# Version2.net
KiCad netlist of a schematic drawn in EAGLE
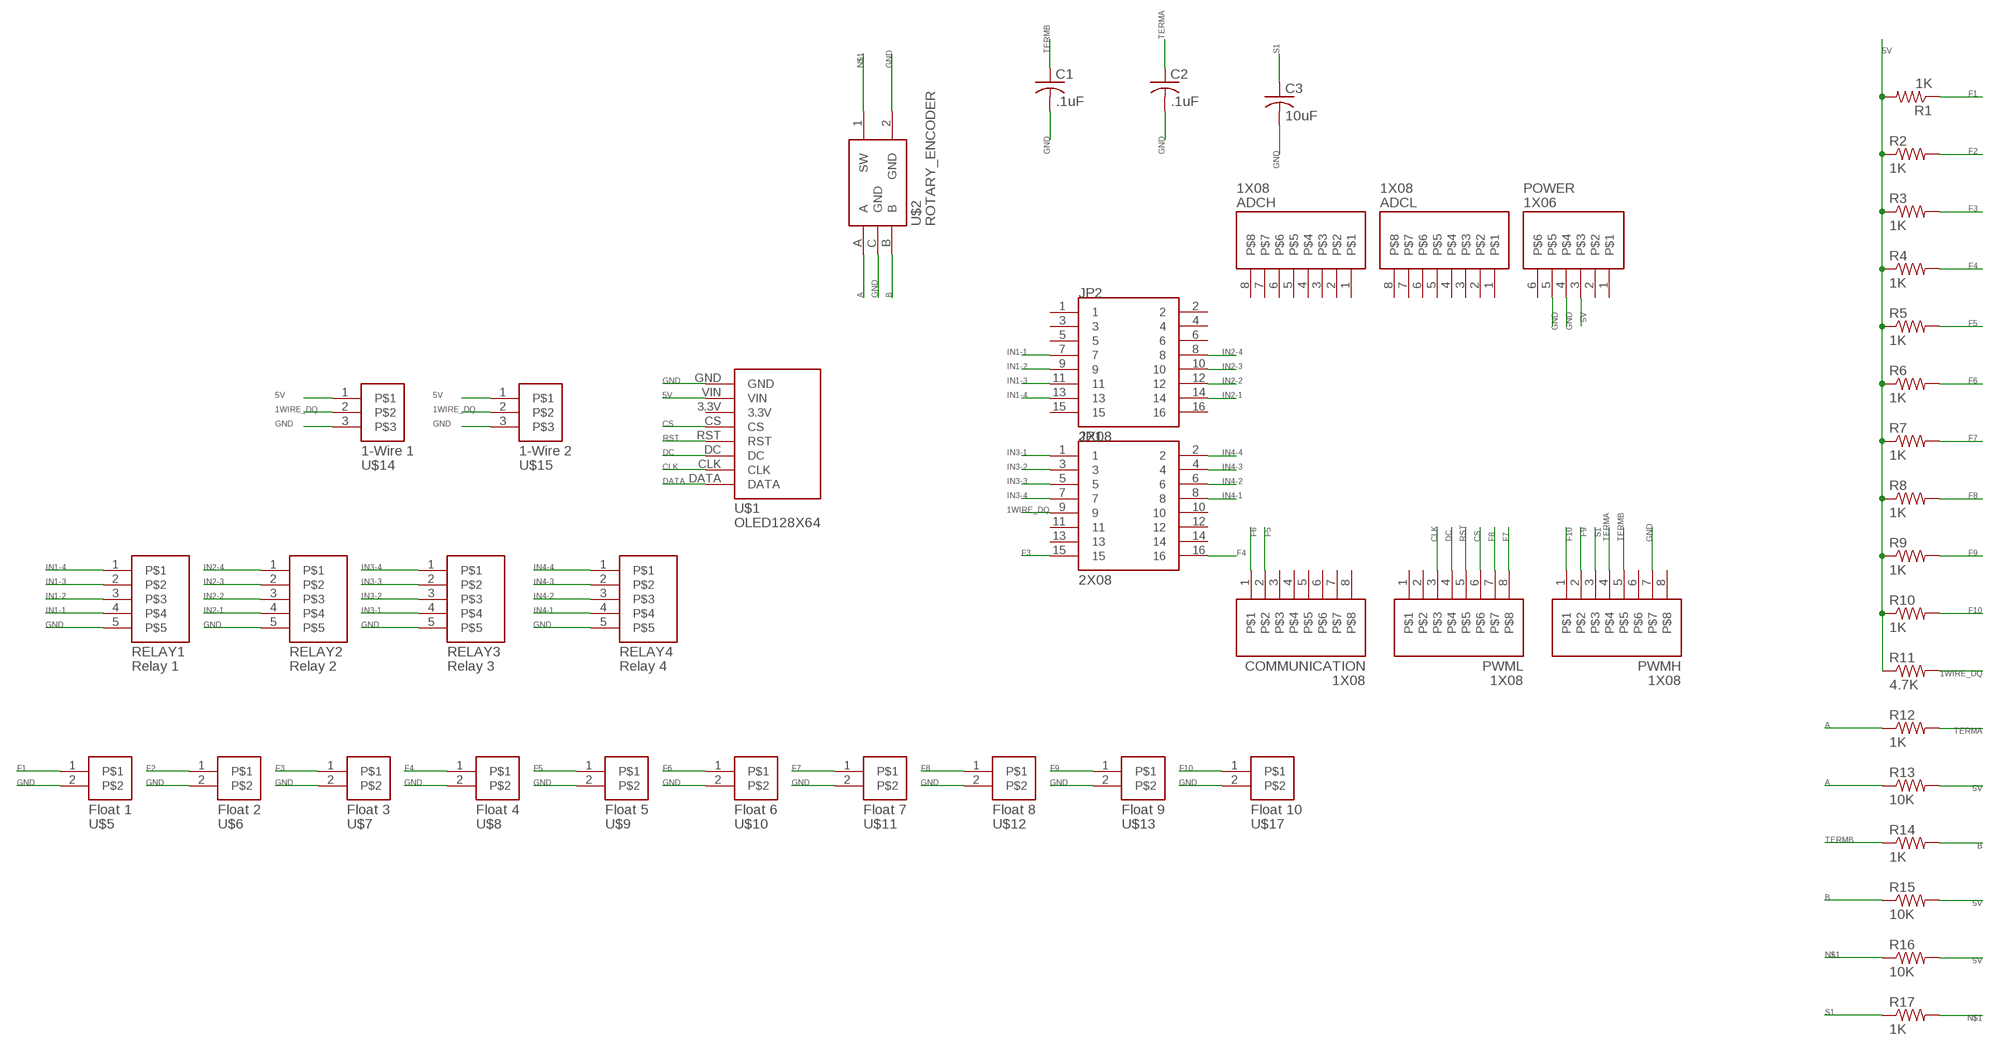
[diagram p0: schematic, sheet 1]

(export (version "E")
  (design (tool "Eeschema 10.0.6"))
  (components
    (comp (ref "ADCH")
      (value "1X08")
      (footprint "eagle-import:1X08_SMT")
      (libsource (lib "eagle-import") (part "1X08"))
    )
    (comp (ref "ADCL")
      (value "1X08")
      (footprint "eagle-import:1X08_SMT")
      (libsource (lib "eagle-import") (part "1X08"))
    )
    (comp (ref "C1")
      (value ".1uF")
      (footprint "eagle-import:C0805K")
      (libsource (lib "eagle-import") (part "C-USC0805K"))
    )
    (comp (ref "C2")
      (value ".1uF")
      (footprint "eagle-import:C0805K")
      (libsource (lib "eagle-import") (part "resistor_C-USC0805K"))
    )
    (comp (ref "C3")
      (value "10uF")
      (footprint "eagle-import:C0805K")
      (libsource (lib "eagle-import") (part "resistor_C-USC0805K"))
    )
    (comp (ref "COMMUNICATION")
      (value "1X08")
      (footprint "eagle-import:1X08_SMT")
      (libsource (lib "eagle-import") (part "1X08"))
    )
    (comp (ref "JP1")
      (value "2X08")
      (footprint "eagle-import:2X08_SMT")
      (libsource (lib "eagle-import") (part "2X08"))
    )
    (comp (ref "JP2")
      (value "2X08")
      (footprint "eagle-import:2X08_SMT")
      (libsource (lib "eagle-import") (part "2X08"))
    )
    (comp (ref "POWER")
      (value "1X06")
      (footprint "eagle-import:1X06_SMT")
      (libsource (lib "eagle-import") (part "1X06"))
    )
    (comp (ref "PWMH")
      (value "1X08")
      (footprint "eagle-import:1X08_SMT")
      (libsource (lib "eagle-import") (part "1X08"))
    )
    (comp (ref "PWML")
      (value "1X08")
      (footprint "eagle-import:1X08_SMT")
      (libsource (lib "eagle-import") (part "1X08"))
    )
    (comp (ref "R1")
      (value "1K")
      (footprint "eagle-import:R0805")
      (libsource (lib "eagle-import") (part "R-US_R0805"))
    )
    (comp (ref "R2")
      (value "1K")
      (footprint "eagle-import:R0805")
      (libsource (lib "eagle-import") (part "R-US_R0805"))
    )
    (comp (ref "R3")
      (value "1K")
      (footprint "eagle-import:R0805")
      (libsource (lib "eagle-import") (part "R-US_R0805"))
    )
    (comp (ref "R4")
      (value "1K")
      (footprint "eagle-import:R0805")
      (libsource (lib "eagle-import") (part "R-US_R0805"))
    )
    (comp (ref "R5")
      (value "1K")
      (footprint "eagle-import:R0805")
      (libsource (lib "eagle-import") (part "R-US_R0805"))
    )
    (comp (ref "R6")
      (value "1K")
      (footprint "eagle-import:R0805")
      (libsource (lib "eagle-import") (part "R-US_R0805"))
    )
    (comp (ref "R7")
      (value "1K")
      (footprint "eagle-import:R0805")
      (libsource (lib "eagle-import") (part "R-US_R0805"))
    )
    (comp (ref "R8")
      (value "1K")
      (footprint "eagle-import:R0805")
      (libsource (lib "eagle-import") (part "R-US_R0805"))
    )
    (comp (ref "R9")
      (value "1K")
      (footprint "eagle-import:R0805")
      (libsource (lib "eagle-import") (part "R-US_R0805"))
    )
    (comp (ref "R10")
      (value "1K")
      (footprint "eagle-import:R0805")
      (libsource (lib "eagle-import") (part "R-US_R0805"))
    )
    (comp (ref "R11")
      (value "4.7K")
      (footprint "eagle-import:R0805")
      (libsource (lib "eagle-import") (part "R-US_R0805"))
    )
    (comp (ref "R12")
      (value "1K")
      (footprint "eagle-import:R0805")
      (libsource (lib "eagle-import") (part "R-US_R0805"))
    )
    (comp (ref "R13")
      (value "10K")
      (footprint "eagle-import:R0805")
      (libsource (lib "eagle-import") (part "R-US_R0805"))
    )
    (comp (ref "R14")
      (value "1K")
      (footprint "eagle-import:R0805")
      (libsource (lib "eagle-import") (part "R-US_R0805"))
    )
    (comp (ref "R15")
      (value "10K")
      (footprint "eagle-import:R0805")
      (libsource (lib "eagle-import") (part "R-US_R0805"))
    )
    (comp (ref "R16")
      (value "10K")
      (footprint "eagle-import:R0805")
      (libsource (lib "eagle-import") (part "R-US_R0805"))
    )
    (comp (ref "R17")
      (value "1K")
      (footprint "eagle-import:R0805")
      (libsource (lib "eagle-import") (part "R-US_R0805"))
    )
    (comp (ref "RELAY1")
      (value "Relay 1")
      (footprint "eagle-import:5PIN-MOLEX-HEADER-W-PEGS")
      (libsource (lib "eagle-import") (part "5PIN"))
    )
    (comp (ref "RELAY2")
      (value "Relay 2")
      (footprint "eagle-import:5PIN-MOLEX-HEADER-W-PEGS")
      (libsource (lib "eagle-import") (part "5PIN"))
    )
    (comp (ref "RELAY3")
      (value "Relay 3")
      (footprint "eagle-import:5PIN-MOLEX-HEADER-W-PEGS")
      (libsource (lib "eagle-import") (part "5PIN"))
    )
    (comp (ref "RELAY4")
      (value "Relay 4")
      (footprint "eagle-import:5PIN-MOLEX-HEADER-W-PEGS")
      (libsource (lib "eagle-import") (part "5PIN"))
    )
    (comp (ref "U$1")
      (value "OLED128X64")
      (footprint "eagle-import:OLED128X64")
      (libsource (lib "eagle-import") (part "OLED128X64"))
    )
    (comp (ref "U$2")
      (value "ROTARY_ENCODER")
      (footprint "eagle-import:PEC11-4215F-S24")
      (libsource (lib "eagle-import") (part "PEC11-4215F-S24"))
    )
    (comp (ref "U$5")
      (value "Float 1")
      (footprint "eagle-import:2PIN-MOLEX-HEADER-W-PEGS")
      (libsource (lib "eagle-import") (part "2PIN"))
    )
    (comp (ref "U$6")
      (value "Float 2")
      (footprint "eagle-import:2PIN-MOLEX-HEADER-W-PEGS")
      (libsource (lib "eagle-import") (part "2PIN"))
    )
    (comp (ref "U$7")
      (value "Float 3")
      (footprint "eagle-import:2PIN-MOLEX-HEADER-W-PEGS")
      (libsource (lib "eagle-import") (part "2PIN"))
    )
    (comp (ref "U$8")
      (value "Float 4")
      (footprint "eagle-import:2PIN-MOLEX-HEADER-W-PEGS")
      (libsource (lib "eagle-import") (part "2PIN"))
    )
    (comp (ref "U$9")
      (value "Float 5")
      (footprint "eagle-import:2PIN-MOLEX-HEADER-W-PEGS")
      (libsource (lib "eagle-import") (part "2PIN"))
    )
    (comp (ref "U$10")
      (value "Float 6")
      (footprint "eagle-import:2PIN-MOLEX-HEADER-W-PEGS")
      (libsource (lib "eagle-import") (part "2PIN"))
    )
    (comp (ref "U$11")
      (value "Float 7")
      (footprint "eagle-import:2PIN-MOLEX-HEADER-W-PEGS")
      (libsource (lib "eagle-import") (part "2PIN"))
    )
    (comp (ref "U$12")
      (value "Float 8")
      (footprint "eagle-import:2PIN-MOLEX-HEADER-W-PEGS")
      (libsource (lib "eagle-import") (part "2PIN"))
    )
    (comp (ref "U$13")
      (value "Float 9")
      (footprint "eagle-import:2PIN-MOLEX-HEADER-W-PEGS")
      (libsource (lib "eagle-import") (part "2PIN"))
    )
    (comp (ref "U$14")
      (value "1-Wire 1")
      (footprint "eagle-import:3PIN-MOLEX-HEADER-W-PEGS")
      (libsource (lib "eagle-import") (part "3PIN"))
    )
    (comp (ref "U$15")
      (value "1-Wire 2")
      (footprint "eagle-import:3PIN-MOLEX-HEADER-W-PEGS")
      (libsource (lib "eagle-import") (part "3PIN"))
    )
    (comp (ref "U$17")
      (value "Float 10")
      (footprint "eagle-import:2PIN-MOLEX-HEADER-W-PEGS")
      (libsource (lib "eagle-import") (part "2PIN"))
    )
  )
  (nets
    (net (code "1") (name "/1WIRE_DQ") (class "Default")
      (node (ref "JP1") (pin "9") (pinfunction "9_9") (pintype "bidirectional"))
      (node (ref "R11") (pin "2") (pinfunction "2_2") (pintype "passive"))
      (node (ref "U$14") (pin "2") (pinfunction "P$2_2") (pintype "bidirectional"))
      (node (ref "U$15") (pin "2") (pinfunction "P$2_2") (pintype "bidirectional"))
    )
    (net (code "2") (name "/5V") (class "Default")
      (node (ref "POWER") (pin "3") (pinfunction "P$3_3") (pintype "bidirectional"))
      (node (ref "R1") (pin "2") (pinfunction "2_2") (pintype "passive"))
      (node (ref "R10") (pin "1") (pinfunction "1_1") (pintype "passive"))
      (node (ref "R11") (pin "1") (pinfunction "1_1") (pintype "passive"))
      (node (ref "R13") (pin "2") (pinfunction "2_2") (pintype "passive"))
      (node (ref "R15") (pin "2") (pinfunction "2_2") (pintype "passive"))
      (node (ref "R16") (pin "2") (pinfunction "2_2") (pintype "passive"))
      (node (ref "R2") (pin "1") (pinfunction "1_1") (pintype "passive"))
      (node (ref "R3") (pin "1") (pinfunction "1_1") (pintype "passive"))
      (node (ref "R4") (pin "1") (pinfunction "1_1") (pintype "passive"))
      (node (ref "R5") (pin "1") (pinfunction "1_1") (pintype "passive"))
      (node (ref "R6") (pin "1") (pinfunction "1_1") (pintype "passive"))
      (node (ref "R7") (pin "1") (pinfunction "1_1") (pintype "passive"))
      (node (ref "R8") (pin "1") (pinfunction "1_1") (pintype "passive"))
      (node (ref "R9") (pin "1") (pinfunction "1_1") (pintype "passive"))
      (node (ref "U$1") (pin "VIN") (pinfunction "VIN_VIN") (pintype "bidirectional"))
      (node (ref "U$14") (pin "1") (pinfunction "P$1_1") (pintype "bidirectional"))
      (node (ref "U$15") (pin "1") (pinfunction "P$1_1") (pintype "bidirectional"))
    )
    (net (code "3") (name "/A") (class "Default")
      (node (ref "R12") (pin "1") (pinfunction "1_1") (pintype "passive"))
      (node (ref "R13") (pin "1") (pinfunction "1_1") (pintype "passive"))
      (node (ref "U$2") (pin "A") (pinfunction "A_A") (pintype "bidirectional"))
    )
    (net (code "4") (name "/B") (class "Default")
      (node (ref "R14") (pin "2") (pinfunction "2_2") (pintype "passive"))
      (node (ref "R15") (pin "1") (pinfunction "1_1") (pintype "passive"))
      (node (ref "U$2") (pin "B") (pinfunction "B_B") (pintype "bidirectional"))
    )
    (net (code "5") (name "/CLK") (class "Default")
      (node (ref "PWML") (pin "3") (pinfunction "P$3_3") (pintype "bidirectional"))
      (node (ref "U$1") (pin "CLK") (pinfunction "CLK_CLK") (pintype "bidirectional"))
    )
    (net (code "6") (name "/CS") (class "Default")
      (node (ref "PWML") (pin "6") (pinfunction "P$6_6") (pintype "bidirectional"))
      (node (ref "U$1") (pin "CS") (pinfunction "CS_CS") (pintype "bidirectional"))
    )
    (net (code "7") (name "/DATA") (class "Default")
      (node (ref "U$1") (pin "DATA") (pinfunction "DATA_DATA") (pintype "bidirectional"))
    )
    (net (code "8") (name "/DC") (class "Default")
      (node (ref "PWML") (pin "4") (pinfunction "P$4_4") (pintype "bidirectional"))
      (node (ref "U$1") (pin "DC") (pinfunction "DC_DC") (pintype "bidirectional"))
    )
    (net (code "9") (name "/F1") (class "Default")
      (node (ref "R1") (pin "1") (pinfunction "1_1") (pintype "passive"))
      (node (ref "U$5") (pin "1") (pinfunction "P$1_1") (pintype "bidirectional"))
    )
    (net (code "10") (name "/F2") (class "Default")
      (node (ref "R2") (pin "2") (pinfunction "2_2") (pintype "passive"))
      (node (ref "U$6") (pin "1") (pinfunction "P$1_1") (pintype "bidirectional"))
    )
    (net (code "11") (name "/F3") (class "Default")
      (node (ref "JP1") (pin "15") (pinfunction "15_15") (pintype "bidirectional"))
      (node (ref "R3") (pin "2") (pinfunction "2_2") (pintype "passive"))
      (node (ref "U$7") (pin "1") (pinfunction "P$1_1") (pintype "bidirectional"))
    )
    (net (code "12") (name "/F4") (class "Default")
      (node (ref "JP1") (pin "16") (pinfunction "16_16") (pintype "bidirectional"))
      (node (ref "R4") (pin "2") (pinfunction "2_2") (pintype "passive"))
      (node (ref "U$8") (pin "1") (pinfunction "P$1_1") (pintype "bidirectional"))
    )
    (net (code "13") (name "/F5") (class "Default")
      (node (ref "COMMUNICATION") (pin "2") (pinfunction "P$2_2") (pintype "bidirectional"))
      (node (ref "R5") (pin "2") (pinfunction "2_2") (pintype "passive"))
      (node (ref "U$9") (pin "1") (pinfunction "P$1_1") (pintype "bidirectional"))
    )
    (net (code "14") (name "/F6") (class "Default")
      (node (ref "COMMUNICATION") (pin "1") (pinfunction "P$1_1") (pintype "bidirectional"))
      (node (ref "R6") (pin "2") (pinfunction "2_2") (pintype "passive"))
      (node (ref "U$10") (pin "1") (pinfunction "P$1_1") (pintype "bidirectional"))
    )
    (net (code "15") (name "/F7") (class "Default")
      (node (ref "PWML") (pin "8") (pinfunction "P$8_8") (pintype "bidirectional"))
      (node (ref "R7") (pin "2") (pinfunction "2_2") (pintype "passive"))
      (node (ref "U$11") (pin "1") (pinfunction "P$1_1") (pintype "bidirectional"))
    )
    (net (code "16") (name "/F8") (class "Default")
      (node (ref "PWML") (pin "7") (pinfunction "P$7_7") (pintype "bidirectional"))
      (node (ref "R8") (pin "2") (pinfunction "2_2") (pintype "passive"))
      (node (ref "U$12") (pin "1") (pinfunction "P$1_1") (pintype "bidirectional"))
    )
    (net (code "17") (name "/F9") (class "Default")
      (node (ref "PWMH") (pin "2") (pinfunction "P$2_2") (pintype "bidirectional"))
      (node (ref "R9") (pin "2") (pinfunction "2_2") (pintype "passive"))
      (node (ref "U$13") (pin "1") (pinfunction "P$1_1") (pintype "bidirectional"))
    )
    (net (code "18") (name "/F10") (class "Default")
      (node (ref "PWMH") (pin "1") (pinfunction "P$1_1") (pintype "bidirectional"))
      (node (ref "R10") (pin "2") (pinfunction "2_2") (pintype "passive"))
      (node (ref "U$17") (pin "1") (pinfunction "P$1_1") (pintype "bidirectional"))
    )
    (net (code "19") (name "/GND") (class "Default")
      (node (ref "C1") (pin "2") (pinfunction "2_2") (pintype "passive"))
      (node (ref "C2") (pin "2") (pinfunction "2_2") (pintype "passive"))
      (node (ref "C3") (pin "2") (pinfunction "2_2") (pintype "passive"))
      (node (ref "POWER") (pin "4") (pinfunction "P$4_4") (pintype "bidirectional"))
      (node (ref "POWER") (pin "5") (pinfunction "P$5_5") (pintype "bidirectional"))
      (node (ref "PWMH") (pin "7") (pinfunction "P$7_7") (pintype "bidirectional"))
      (node (ref "RELAY1") (pin "5") (pinfunction "P$5_5") (pintype "bidirectional"))
      (node (ref "RELAY2") (pin "5") (pinfunction "P$5_5") (pintype "bidirectional"))
      (node (ref "RELAY3") (pin "5") (pinfunction "P$5_5") (pintype "bidirectional"))
      (node (ref "RELAY4") (pin "5") (pinfunction "P$5_5") (pintype "bidirectional"))
      (node (ref "U$1") (pin "GND") (pinfunction "GND_GND") (pintype "bidirectional"))
      (node (ref "U$10") (pin "2") (pinfunction "P$2_2") (pintype "bidirectional"))
      (node (ref "U$11") (pin "2") (pinfunction "P$2_2") (pintype "bidirectional"))
      (node (ref "U$12") (pin "2") (pinfunction "P$2_2") (pintype "bidirectional"))
      (node (ref "U$13") (pin "2") (pinfunction "P$2_2") (pintype "bidirectional"))
      (node (ref "U$14") (pin "3") (pinfunction "P$3_3") (pintype "bidirectional"))
      (node (ref "U$15") (pin "3") (pinfunction "P$3_3") (pintype "bidirectional"))
      (node (ref "U$17") (pin "2") (pinfunction "P$2_2") (pintype "bidirectional"))
      (node (ref "U$2") (pin "2") (pinfunction "GND_2") (pintype "bidirectional"))
      (node (ref "U$2") (pin "C") (pinfunction "GND_C") (pintype "bidirectional"))
      (node (ref "U$5") (pin "2") (pinfunction "P$2_2") (pintype "bidirectional"))
      (node (ref "U$6") (pin "2") (pinfunction "P$2_2") (pintype "bidirectional"))
      (node (ref "U$7") (pin "2") (pinfunction "P$2_2") (pintype "bidirectional"))
      (node (ref "U$8") (pin "2") (pinfunction "P$2_2") (pintype "bidirectional"))
      (node (ref "U$9") (pin "2") (pinfunction "P$2_2") (pintype "bidirectional"))
    )
    (net (code "20") (name "/IN1-1") (class "Default")
      (node (ref "JP2") (pin "7") (pinfunction "7_7") (pintype "bidirectional"))
      (node (ref "RELAY1") (pin "4") (pinfunction "P$4_4") (pintype "bidirectional"))
    )
    (net (code "21") (name "/IN1-2") (class "Default")
      (node (ref "JP2") (pin "9") (pinfunction "9_9") (pintype "bidirectional"))
      (node (ref "RELAY1") (pin "3") (pinfunction "P$3_3") (pintype "bidirectional"))
    )
    (net (code "22") (name "/IN1-3") (class "Default")
      (node (ref "JP2") (pin "11") (pinfunction "11_11") (pintype "bidirectional"))
      (node (ref "RELAY1") (pin "2") (pinfunction "P$2_2") (pintype "bidirectional"))
    )
    (net (code "23") (name "/IN1-4") (class "Default")
      (node (ref "JP2") (pin "13") (pinfunction "13_13") (pintype "bidirectional"))
      (node (ref "RELAY1") (pin "1") (pinfunction "P$1_1") (pintype "bidirectional"))
    )
    (net (code "24") (name "/IN2-1") (class "Default")
      (node (ref "JP2") (pin "14") (pinfunction "14_14") (pintype "bidirectional"))
      (node (ref "RELAY2") (pin "4") (pinfunction "P$4_4") (pintype "bidirectional"))
    )
    (net (code "25") (name "/IN2-2") (class "Default")
      (node (ref "JP2") (pin "12") (pinfunction "12_12") (pintype "bidirectional"))
      (node (ref "RELAY2") (pin "3") (pinfunction "P$3_3") (pintype "bidirectional"))
    )
    (net (code "26") (name "/IN2-3") (class "Default")
      (node (ref "JP2") (pin "10") (pinfunction "10_10") (pintype "bidirectional"))
      (node (ref "RELAY2") (pin "2") (pinfunction "P$2_2") (pintype "bidirectional"))
    )
    (net (code "27") (name "/IN2-4") (class "Default")
      (node (ref "JP2") (pin "8") (pinfunction "8_8") (pintype "bidirectional"))
      (node (ref "RELAY2") (pin "1") (pinfunction "P$1_1") (pintype "bidirectional"))
    )
    (net (code "28") (name "/IN3-1") (class "Default")
      (node (ref "JP1") (pin "1") (pinfunction "1_1") (pintype "bidirectional"))
      (node (ref "RELAY3") (pin "4") (pinfunction "P$4_4") (pintype "bidirectional"))
    )
    (net (code "29") (name "/IN3-2") (class "Default")
      (node (ref "JP1") (pin "3") (pinfunction "3_3") (pintype "bidirectional"))
      (node (ref "RELAY3") (pin "3") (pinfunction "P$3_3") (pintype "bidirectional"))
    )
    (net (code "30") (name "/IN3-3") (class "Default")
      (node (ref "JP1") (pin "5") (pinfunction "5_5") (pintype "bidirectional"))
      (node (ref "RELAY3") (pin "2") (pinfunction "P$2_2") (pintype "bidirectional"))
    )
    (net (code "31") (name "/IN3-4") (class "Default")
      (node (ref "JP1") (pin "7") (pinfunction "7_7") (pintype "bidirectional"))
      (node (ref "RELAY3") (pin "1") (pinfunction "P$1_1") (pintype "bidirectional"))
    )
    (net (code "32") (name "/IN4-1") (class "Default")
      (node (ref "JP1") (pin "8") (pinfunction "8_8") (pintype "bidirectional"))
      (node (ref "RELAY4") (pin "4") (pinfunction "P$4_4") (pintype "bidirectional"))
    )
    (net (code "33") (name "/IN4-2") (class "Default")
      (node (ref "JP1") (pin "6") (pinfunction "6_6") (pintype "bidirectional"))
      (node (ref "RELAY4") (pin "3") (pinfunction "P$3_3") (pintype "bidirectional"))
    )
    (net (code "34") (name "/IN4-3") (class "Default")
      (node (ref "JP1") (pin "4") (pinfunction "4_4") (pintype "bidirectional"))
      (node (ref "RELAY4") (pin "2") (pinfunction "P$2_2") (pintype "bidirectional"))
    )
    (net (code "35") (name "/IN4-4") (class "Default")
      (node (ref "JP1") (pin "2") (pinfunction "2_2") (pintype "bidirectional"))
      (node (ref "RELAY4") (pin "1") (pinfunction "P$1_1") (pintype "bidirectional"))
    )
    (net (code "36") (name "/N$1") (class "Default")
      (node (ref "R16") (pin "1") (pinfunction "1_1") (pintype "passive"))
      (node (ref "R17") (pin "2") (pinfunction "2_2") (pintype "passive"))
      (node (ref "U$2") (pin "1") (pinfunction "SW_1") (pintype "bidirectional"))
    )
    (net (code "37") (name "/RST") (class "Default")
      (node (ref "PWML") (pin "5") (pinfunction "P$5_5") (pintype "bidirectional"))
      (node (ref "U$1") (pin "RST") (pinfunction "RST_RST") (pintype "bidirectional"))
    )
    (net (code "38") (name "/S1") (class "Default")
      (node (ref "C3") (pin "1") (pinfunction "1_1") (pintype "passive"))
      (node (ref "PWMH") (pin "3") (pinfunction "P$3_3") (pintype "bidirectional"))
      (node (ref "R17") (pin "1") (pinfunction "1_1") (pintype "passive"))
    )
    (net (code "39") (name "/TERMA") (class "Default")
      (node (ref "C2") (pin "1") (pinfunction "1_1") (pintype "passive"))
      (node (ref "PWMH") (pin "4") (pinfunction "P$4_4") (pintype "bidirectional"))
      (node (ref "R12") (pin "2") (pinfunction "2_2") (pintype "passive"))
    )
    (net (code "40") (name "/TERMB") (class "Default")
      (node (ref "C1") (pin "1") (pinfunction "1_1") (pintype "passive"))
      (node (ref "PWMH") (pin "5") (pinfunction "P$5_5") (pintype "bidirectional"))
      (node (ref "R14") (pin "1") (pinfunction "1_1") (pintype "passive"))
    )
    (net (code "41") (name "unconnected-(ADCH-P$1-Pad1)") (class "Default")
      (node (ref "ADCH") (pin "1") (pinfunction "P$1_1") (pintype "bidirectional"))
    )
    (net (code "42") (name "unconnected-(ADCH-P$2-Pad2)") (class "Default")
      (node (ref "ADCH") (pin "2") (pinfunction "P$2_2") (pintype "bidirectional"))
    )
    (net (code "43") (name "unconnected-(ADCH-P$3-Pad3)") (class "Default")
      (node (ref "ADCH") (pin "3") (pinfunction "P$3_3") (pintype "bidirectional"))
    )
    (net (code "44") (name "unconnected-(ADCH-P$4-Pad4)") (class "Default")
      (node (ref "ADCH") (pin "4") (pinfunction "P$4_4") (pintype "bidirectional"))
    )
    (net (code "45") (name "unconnected-(ADCH-P$5-Pad5)") (class "Default")
      (node (ref "ADCH") (pin "5") (pinfunction "P$5_5") (pintype "bidirectional"))
    )
    (net (code "46") (name "unconnected-(ADCH-P$6-Pad6)") (class "Default")
      (node (ref "ADCH") (pin "6") (pinfunction "P$6_6") (pintype "bidirectional"))
    )
    (net (code "47") (name "unconnected-(ADCH-P$7-Pad7)") (class "Default")
      (node (ref "ADCH") (pin "7") (pinfunction "P$7_7") (pintype "bidirectional"))
    )
    (net (code "48") (name "unconnected-(ADCH-P$8-Pad8)") (class "Default")
      (node (ref "ADCH") (pin "8") (pinfunction "P$8_8") (pintype "bidirectional"))
    )
    (net (code "49") (name "unconnected-(ADCL-P$1-Pad1)") (class "Default")
      (node (ref "ADCL") (pin "1") (pinfunction "P$1_1") (pintype "bidirectional"))
    )
    (net (code "50") (name "unconnected-(ADCL-P$2-Pad2)") (class "Default")
      (node (ref "ADCL") (pin "2") (pinfunction "P$2_2") (pintype "bidirectional"))
    )
    (net (code "51") (name "unconnected-(ADCL-P$3-Pad3)") (class "Default")
      (node (ref "ADCL") (pin "3") (pinfunction "P$3_3") (pintype "bidirectional"))
    )
    (net (code "52") (name "unconnected-(ADCL-P$4-Pad4)") (class "Default")
      (node (ref "ADCL") (pin "4") (pinfunction "P$4_4") (pintype "bidirectional"))
    )
    (net (code "53") (name "unconnected-(ADCL-P$5-Pad5)") (class "Default")
      (node (ref "ADCL") (pin "5") (pinfunction "P$5_5") (pintype "bidirectional"))
    )
    (net (code "54") (name "unconnected-(ADCL-P$6-Pad6)") (class "Default")
      (node (ref "ADCL") (pin "6") (pinfunction "P$6_6") (pintype "bidirectional"))
    )
    (net (code "55") (name "unconnected-(ADCL-P$7-Pad7)") (class "Default")
      (node (ref "ADCL") (pin "7") (pinfunction "P$7_7") (pintype "bidirectional"))
    )
    (net (code "56") (name "unconnected-(ADCL-P$8-Pad8)") (class "Default")
      (node (ref "ADCL") (pin "8") (pinfunction "P$8_8") (pintype "bidirectional"))
    )
    (net (code "57") (name "unconnected-(COMMUNICATION-P$3-Pad3)") (class "Default")
      (node (ref "COMMUNICATION") (pin "3") (pinfunction "P$3_3") (pintype "bidirectional"))
    )
    (net (code "58") (name "unconnected-(COMMUNICATION-P$4-Pad4)") (class "Default")
      (node (ref "COMMUNICATION") (pin "4") (pinfunction "P$4_4") (pintype "bidirectional"))
    )
    (net (code "59") (name "unconnected-(COMMUNICATION-P$5-Pad5)") (class "Default")
      (node (ref "COMMUNICATION") (pin "5") (pinfunction "P$5_5") (pintype "bidirectional"))
    )
    (net (code "60") (name "unconnected-(COMMUNICATION-P$6-Pad6)") (class "Default")
      (node (ref "COMMUNICATION") (pin "6") (pinfunction "P$6_6") (pintype "bidirectional"))
    )
    (net (code "61") (name "unconnected-(COMMUNICATION-P$7-Pad7)") (class "Default")
      (node (ref "COMMUNICATION") (pin "7") (pinfunction "P$7_7") (pintype "bidirectional"))
    )
    (net (code "62") (name "unconnected-(COMMUNICATION-P$8-Pad8)") (class "Default")
      (node (ref "COMMUNICATION") (pin "8") (pinfunction "P$8_8") (pintype "bidirectional"))
    )
    (net (code "63") (name "unconnected-(JP1-Pad10)") (class "Default")
      (node (ref "JP1") (pin "10") (pinfunction "10_10") (pintype "bidirectional"))
    )
    (net (code "64") (name "unconnected-(JP1-Pad11)") (class "Default")
      (node (ref "JP1") (pin "11") (pinfunction "11_11") (pintype "bidirectional"))
    )
    (net (code "65") (name "unconnected-(JP1-Pad12)") (class "Default")
      (node (ref "JP1") (pin "12") (pinfunction "12_12") (pintype "bidirectional"))
    )
    (net (code "66") (name "unconnected-(JP1-Pad13)") (class "Default")
      (node (ref "JP1") (pin "13") (pinfunction "13_13") (pintype "bidirectional"))
    )
    (net (code "67") (name "unconnected-(JP1-Pad14)") (class "Default")
      (node (ref "JP1") (pin "14") (pinfunction "14_14") (pintype "bidirectional"))
    )
    (net (code "68") (name "unconnected-(JP2-Pad1)") (class "Default")
      (node (ref "JP2") (pin "1") (pinfunction "1_1") (pintype "bidirectional"))
    )
    (net (code "69") (name "unconnected-(JP2-Pad2)") (class "Default")
      (node (ref "JP2") (pin "2") (pinfunction "2_2") (pintype "bidirectional"))
    )
    (net (code "70") (name "unconnected-(JP2-Pad3)") (class "Default")
      (node (ref "JP2") (pin "3") (pinfunction "3_3") (pintype "bidirectional"))
    )
    (net (code "71") (name "unconnected-(JP2-Pad4)") (class "Default")
      (node (ref "JP2") (pin "4") (pinfunction "4_4") (pintype "bidirectional"))
    )
    (net (code "72") (name "unconnected-(JP2-Pad5)") (class "Default")
      (node (ref "JP2") (pin "5") (pinfunction "5_5") (pintype "bidirectional"))
    )
    (net (code "73") (name "unconnected-(JP2-Pad6)") (class "Default")
      (node (ref "JP2") (pin "6") (pinfunction "6_6") (pintype "bidirectional"))
    )
    (net (code "74") (name "unconnected-(JP2-Pad15)") (class "Default")
      (node (ref "JP2") (pin "15") (pinfunction "15_15") (pintype "bidirectional"))
    )
    (net (code "75") (name "unconnected-(JP2-Pad16)") (class "Default")
      (node (ref "JP2") (pin "16") (pinfunction "16_16") (pintype "bidirectional"))
    )
    (net (code "76") (name "unconnected-(POWER-P$1-Pad1)") (class "Default")
      (node (ref "POWER") (pin "1") (pinfunction "P$1_1") (pintype "bidirectional"))
    )
    (net (code "77") (name "unconnected-(POWER-P$2-Pad2)") (class "Default")
      (node (ref "POWER") (pin "2") (pinfunction "P$2_2") (pintype "bidirectional"))
    )
    (net (code "78") (name "unconnected-(POWER-P$6-Pad6)") (class "Default")
      (node (ref "POWER") (pin "6") (pinfunction "P$6_6") (pintype "bidirectional"))
    )
    (net (code "79") (name "unconnected-(PWMH-P$6-Pad6)") (class "Default")
      (node (ref "PWMH") (pin "6") (pinfunction "P$6_6") (pintype "bidirectional"))
    )
    (net (code "80") (name "unconnected-(PWMH-P$8-Pad8)") (class "Default")
      (node (ref "PWMH") (pin "8") (pinfunction "P$8_8") (pintype "bidirectional"))
    )
    (net (code "81") (name "unconnected-(PWML-P$1-Pad1)") (class "Default")
      (node (ref "PWML") (pin "1") (pinfunction "P$1_1") (pintype "bidirectional"))
    )
    (net (code "82") (name "unconnected-(PWML-P$2-Pad2)") (class "Default")
      (node (ref "PWML") (pin "2") (pinfunction "P$2_2") (pintype "bidirectional"))
    )
    (net (code "83") (name "unconnected-(U$1-Pad3.3V)") (class "Default")
      (node (ref "U$1") (pin "3.3V") (pinfunction "3.3V_3.3V") (pintype "bidirectional"))
    )
  )
)
